# Dust1_Motherboard_BTB.net
KiCad netlist of a schematic drawn in Altium Designer
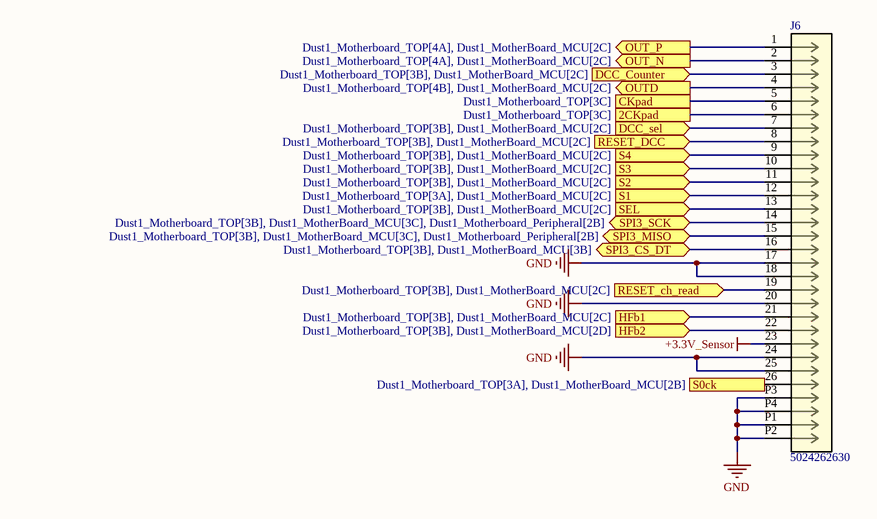
[diagram p0: Dust1_Motherboard_BTB.SchDoc]

(export (version "E")
  (design (tool "Eeschema 10.0.6"))
  (components
    (comp (ref "J6")
      (value "5024262630")
      (footprint "CON_5024262630_MOL")
      (fields (field (name "COPYRIGHT") "Copyright (C) 2025 Ultra Librarian. All rights reserved."))
      (libsource (lib "I3N - LABSAMP") (part "5024262630"))
    )
  )
  (nets
    (net (code "1") (name "+3.3V_Sensor") (class "Default")
      (node (ref "J6") (pin "23") (pinfunction "23_23") (pintype "passive"))
    )
    (net (code "2") (name "/2CKpad") (class "Default")
      (node (ref "J6") (pin "6") (pinfunction "6_6") (pintype "passive"))
    )
    (net (code "3") (name "/CKpad") (class "Default")
      (node (ref "J6") (pin "5") (pinfunction "5_5") (pintype "passive"))
    )
    (net (code "4") (name "/DCC_Counter") (class "Default")
      (node (ref "J6") (pin "3") (pinfunction "3_3") (pintype "passive"))
    )
    (net (code "5") (name "/DCC_sel") (class "Default")
      (node (ref "J6") (pin "7") (pinfunction "7_7") (pintype "passive"))
    )
    (net (code "6") (name "/HFb1") (class "Default")
      (node (ref "J6") (pin "21") (pinfunction "21_21") (pintype "passive"))
    )
    (net (code "7") (name "/HFb2") (class "Default")
      (node (ref "J6") (pin "22") (pinfunction "22_22") (pintype "passive"))
    )
    (net (code "8") (name "/OUTD") (class "Default")
      (node (ref "J6") (pin "4") (pinfunction "4_4") (pintype "passive"))
    )
    (net (code "9") (name "/OUT_N") (class "Default")
      (node (ref "J6") (pin "2") (pinfunction "2_2") (pintype "passive"))
    )
    (net (code "10") (name "/OUT_P") (class "Default")
      (node (ref "J6") (pin "1") (pinfunction "1_1") (pintype "passive"))
    )
    (net (code "11") (name "/RESET_DCC") (class "Default")
      (node (ref "J6") (pin "8") (pinfunction "8_8") (pintype "passive"))
    )
    (net (code "12") (name "/RESET_ch_read") (class "Default")
      (node (ref "J6") (pin "19") (pinfunction "19_19") (pintype "passive"))
    )
    (net (code "13") (name "/S0ck") (class "Default")
      (node (ref "J6") (pin "26") (pinfunction "26_26") (pintype "passive"))
    )
    (net (code "14") (name "/S1") (class "Default")
      (node (ref "J6") (pin "12") (pinfunction "12_12") (pintype "passive"))
    )
    (net (code "15") (name "/S2") (class "Default")
      (node (ref "J6") (pin "11") (pinfunction "11_11") (pintype "passive"))
    )
    (net (code "16") (name "/S3") (class "Default")
      (node (ref "J6") (pin "10") (pinfunction "10_10") (pintype "passive"))
    )
    (net (code "17") (name "/S4") (class "Default")
      (node (ref "J6") (pin "9") (pinfunction "9_9") (pintype "passive"))
    )
    (net (code "18") (name "/SEL") (class "Default")
      (node (ref "J6") (pin "13") (pinfunction "13_13") (pintype "passive"))
    )
    (net (code "19") (name "/SPI3_CS_DT") (class "Default")
      (node (ref "J6") (pin "16") (pinfunction "16_16") (pintype "passive"))
    )
    (net (code "20") (name "/SPI3_MISO") (class "Default")
      (node (ref "J6") (pin "15") (pinfunction "15_15") (pintype "passive"))
    )
    (net (code "21") (name "/SPI3_SCK") (class "Default")
      (node (ref "J6") (pin "14") (pinfunction "14_14") (pintype "passive"))
    )
    (net (code "22") (name "GND") (class "Default")
      (node (ref "J6") (pin "17") (pinfunction "17_17") (pintype "passive"))
      (node (ref "J6") (pin "18") (pinfunction "18_18") (pintype "passive"))
      (node (ref "J6") (pin "20") (pinfunction "20_20") (pintype "passive"))
      (node (ref "J6") (pin "24") (pinfunction "24_24") (pintype "passive"))
      (node (ref "J6") (pin "25") (pinfunction "25_25") (pintype "passive"))
      (node (ref "J6") (pin "P1") (pinfunction "P1_P1") (pintype "passive"))
      (node (ref "J6") (pin "P2") (pinfunction "P2_P2") (pintype "passive"))
      (node (ref "J6") (pin "P3") (pinfunction "P3_P3") (pintype "passive"))
      (node (ref "J6") (pin "P4") (pinfunction "P4_P4") (pintype "passive"))
    )
  )
)
